# PowerConversionBoard-schematic.net
KiCad netlist of a schematic drawn in EAGLE
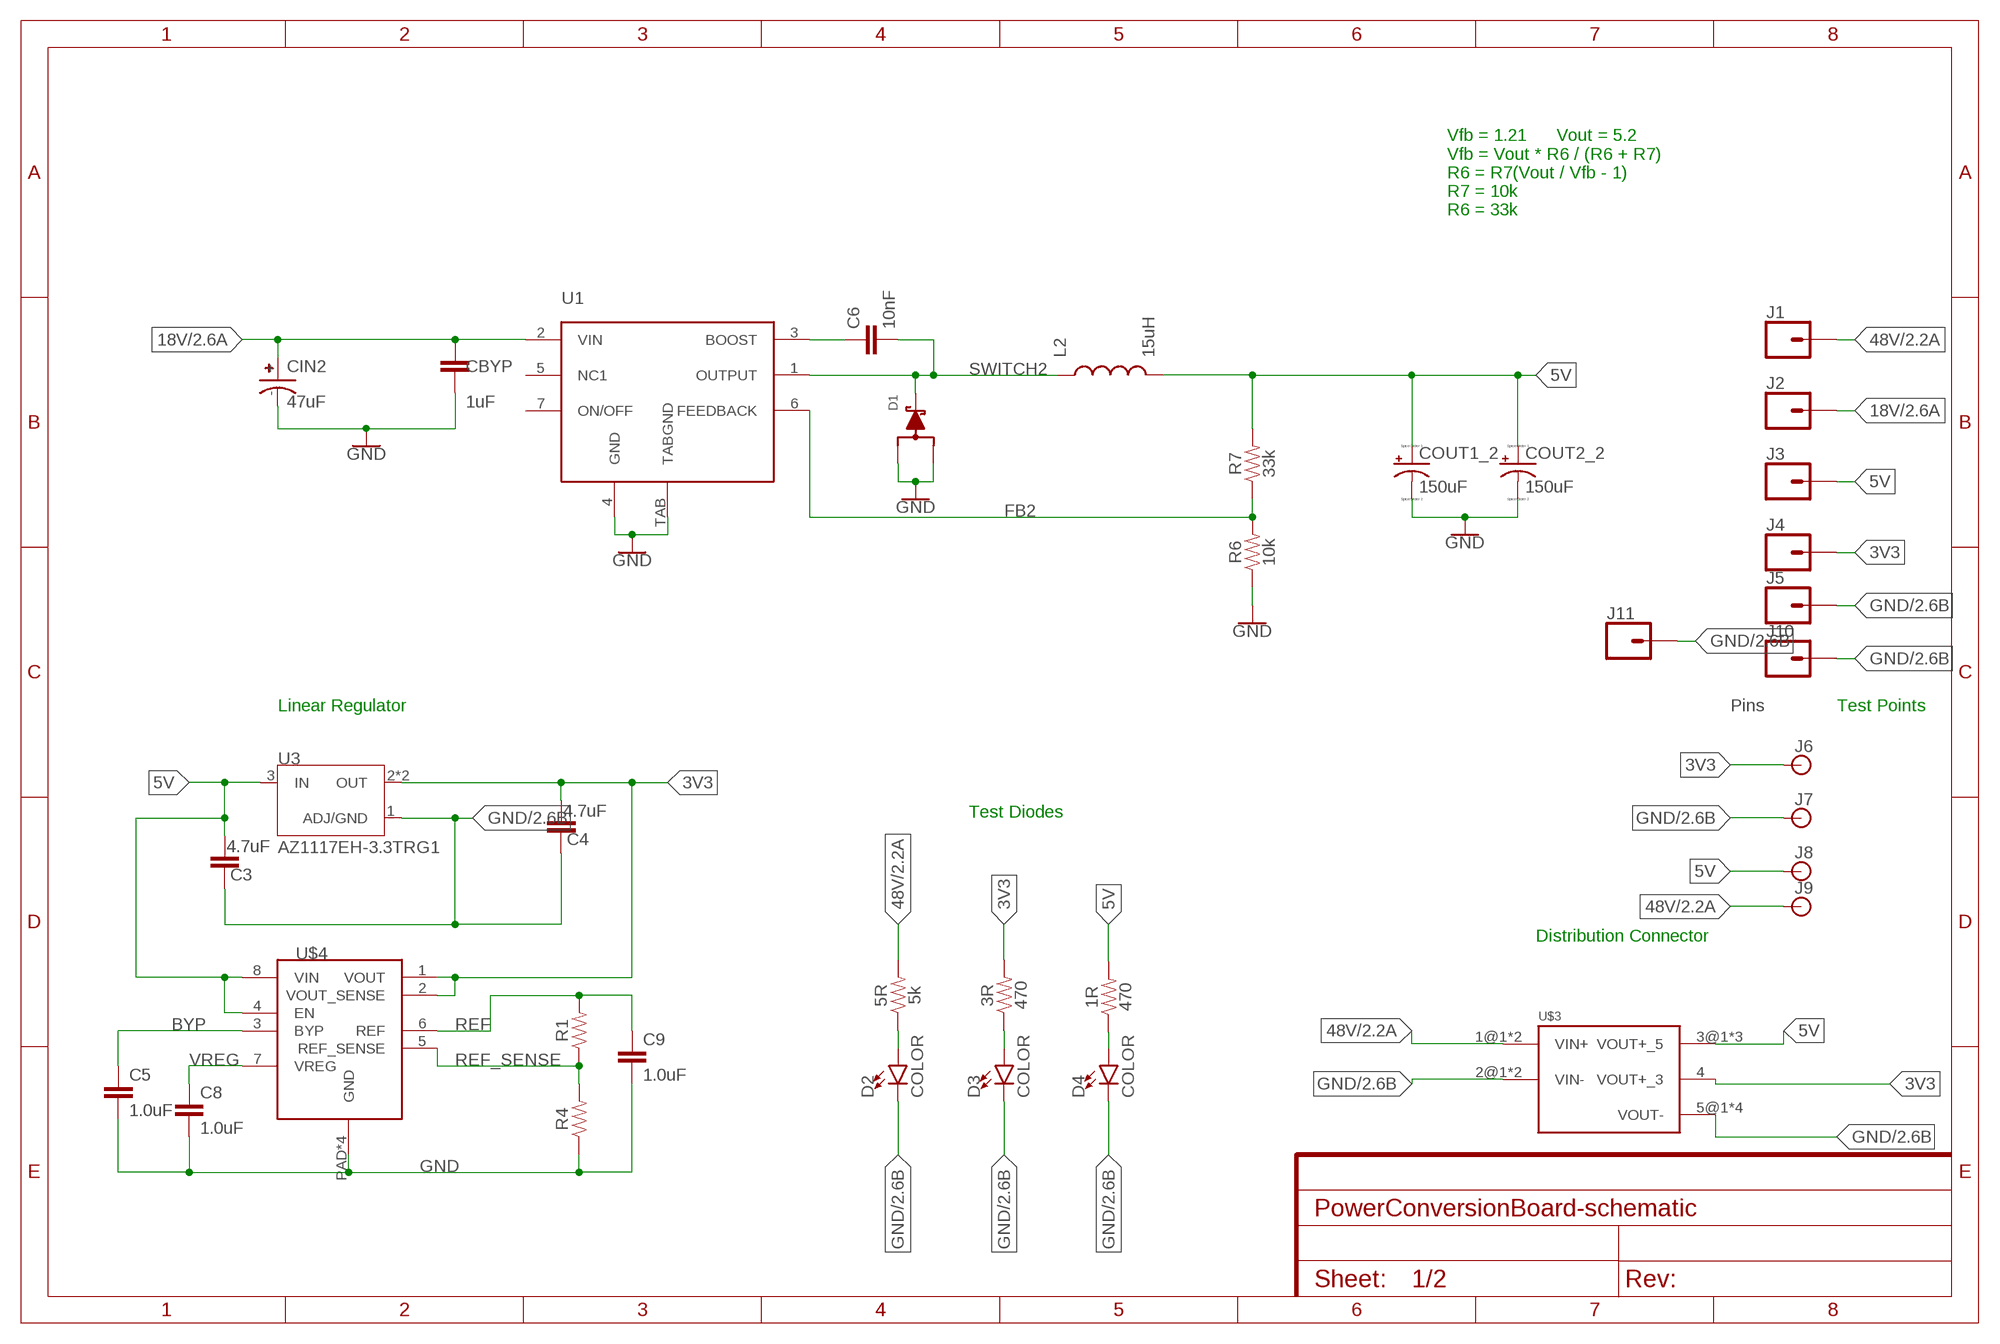
[diagram p0: schematic, sheet 1]
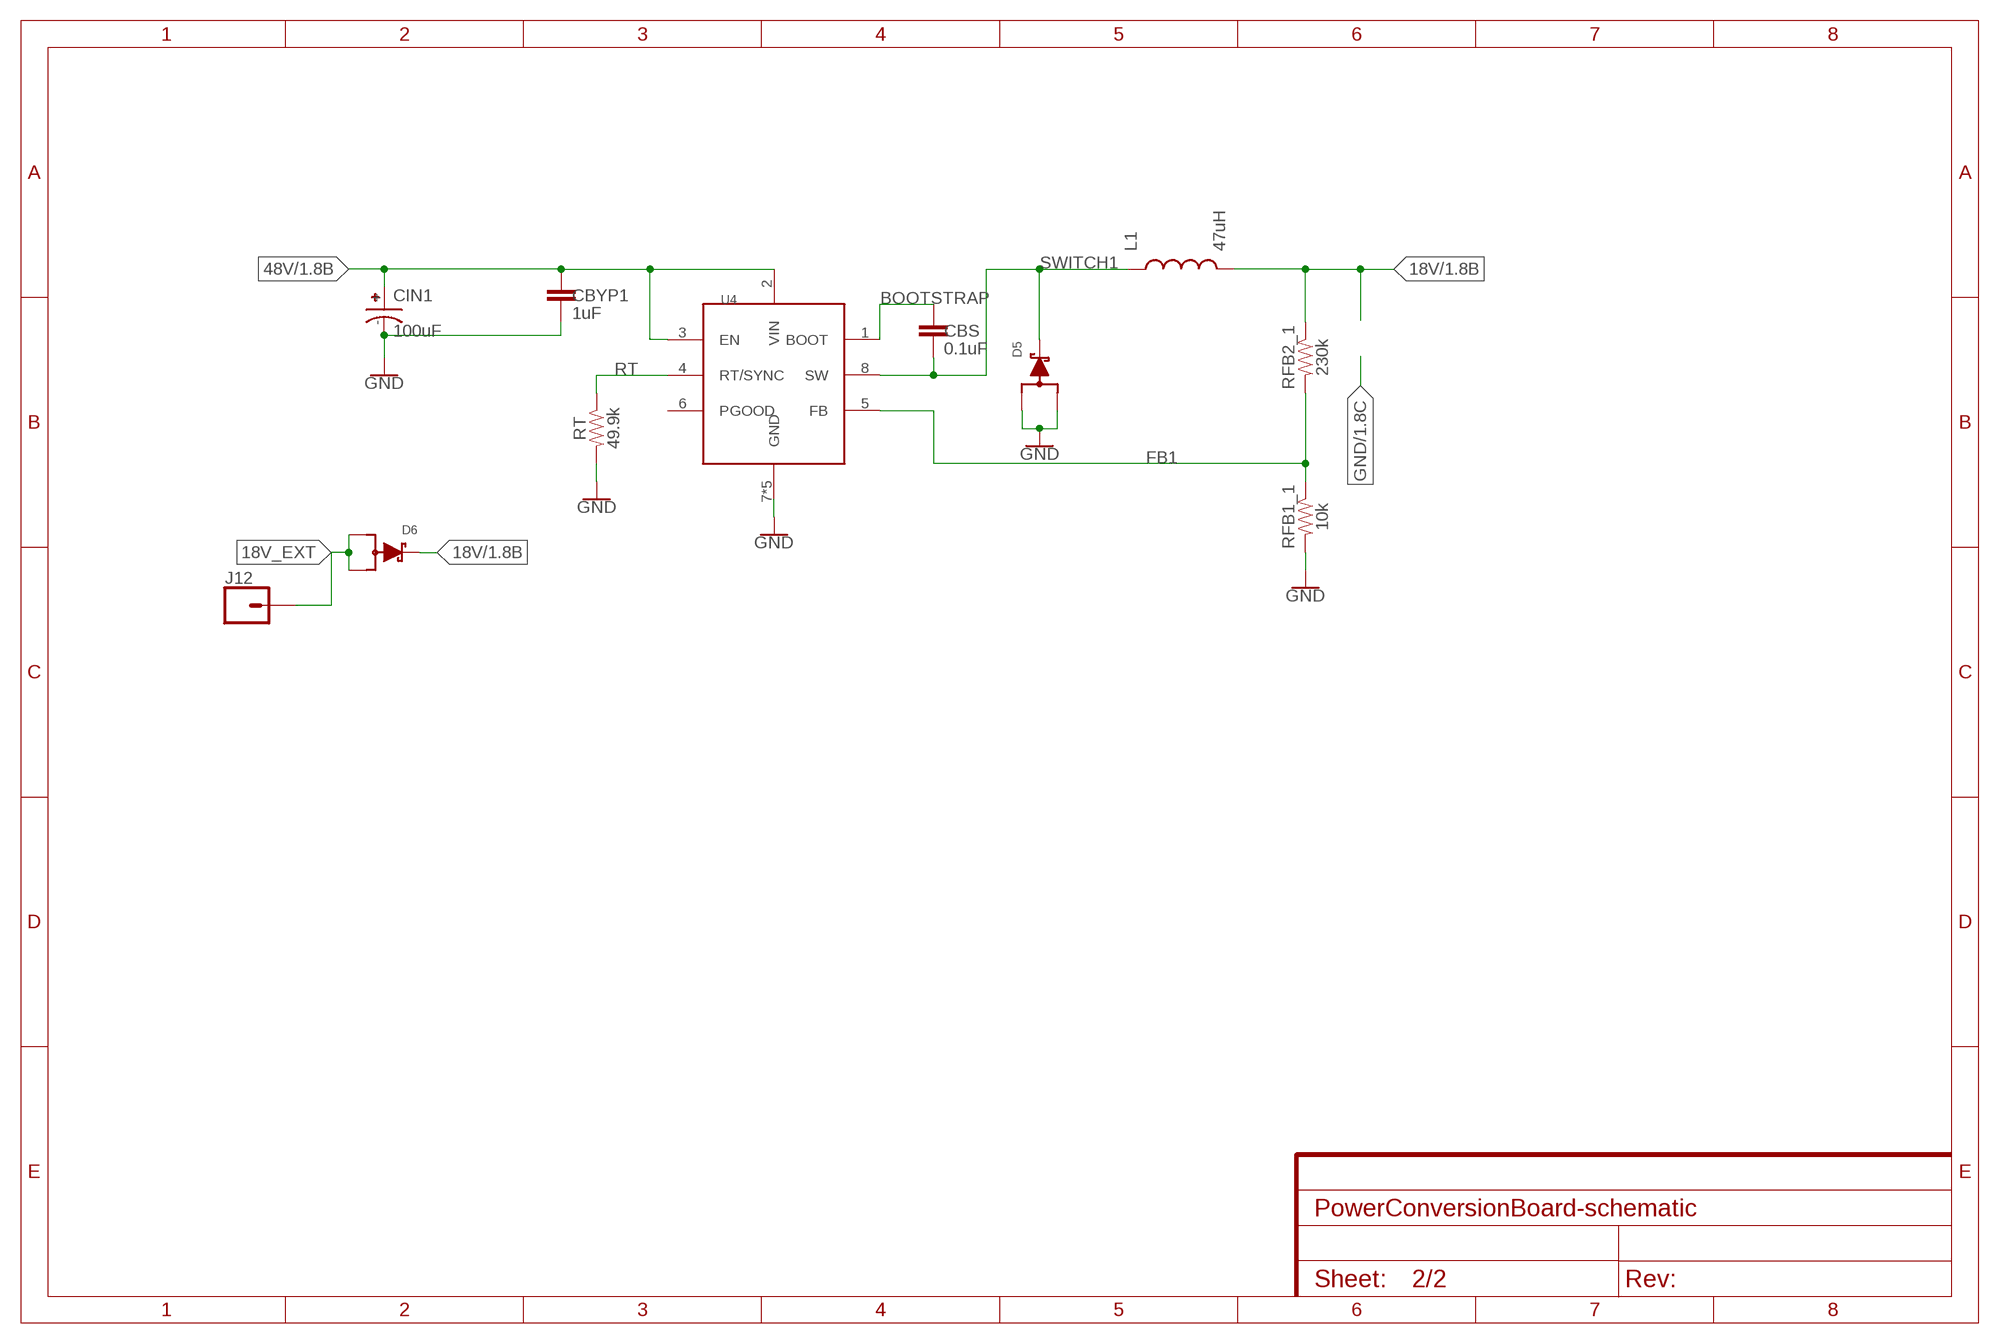
[diagram p1: schematic, sheet 2]

(export (version "E")
  (design (tool "Eeschema 10.0.6"))
  (components
    (comp (ref "CBS")
      (value "0.1uF")
      (footprint "eagle-import:0603")
      (libsource (lib "eagle-import") (part "3.3NF-0603-100V-10%"))
    )
    (comp (ref "CBYP1")
      (value "1uF")
      (footprint "eagle-import:0603")
      (libsource (lib "eagle-import") (part "3.3NF-0603-100V-10%"))
    )
    (comp (ref "CIN1")
      (value "100uF")
      (footprint "eagle-import:CAPAE1030X1050N")
      (fields
        (field (name "ARROW_PART_NUMBER") "UCM1H331MNL1GS")
        (field (name "MOUSER_PART_NUMBER") "647-UCM1H331MNL1GS")
      )
      (libsource (lib "eagle-import") (part "UCM1H331MNL1GS"))
    )
    (comp (ref "D5")
      (value "SWITCHMODE_SCHOTTKY")
      (footprint "eagle-import:DPAK-3")
      (libsource (lib "eagle-import") (part "SWITCHMODE_SCHOTTKY"))
    )
    (comp (ref "D6")
      (value "SWITCHMODE_SCHOTTKY")
      (footprint "eagle-import:DPAK-3")
      (libsource (lib "eagle-import") (part "SWITCHMODE_SCHOTTKY"))
    )
    (comp (ref "J12")
      (value "CONN_01")
      (footprint "eagle-import:1X01")
      (libsource (lib "eagle-import") (part "CONN_01"))
    )
    (comp (ref "L1")
      (value "47uH")
      (footprint "eagle-import:HCMA1305")
      (libsource (lib "eagle-import") (part "HCMA1305"))
    )
    (comp (ref "RFB1_1")
      (value "10k")
      (footprint "eagle-import:0603")
      (libsource (lib "eagle-import") (part "RESISTOR0603"))
    )
    (comp (ref "RFB2_1")
      (value "230k")
      (footprint "eagle-import:0603")
      (libsource (lib "eagle-import") (part "RESISTOR0603"))
    )
    (comp (ref "RT")
      (value "49.9k")
      (footprint "eagle-import:0603")
      (libsource (lib "eagle-import") (part "RESISTOR0603"))
    )
    (comp (ref "U4")
      (value "LMR16020")
      (footprint "eagle-import:8-SOIC-EP")
      (libsource (lib "eagle-import") (part "LMR16020"))
    )
    (comp (ref "1R")
      (value "470")
      (footprint "eagle-import:0603")
      (libsource (lib "eagle-import") (part "470OHM-0603-1/10W-1%"))
    )
    (comp (ref "3R")
      (value "470")
      (footprint "eagle-import:0603")
      (libsource (lib "eagle-import") (part "470OHM-0603-1/10W-1%"))
    )
    (comp (ref "5R")
      (value "5k")
      (footprint "eagle-import:0603")
      (libsource (lib "eagle-import") (part "470OHM-0603-1/10W-1%"))
    )
    (comp (ref "C3")
      (value "4.7uF")
      (footprint "eagle-import:0603")
      (libsource (lib "eagle-import") (part "12PF-0603-50V-5%"))
    )
    (comp (ref "C4")
      (value "4.7uF")
      (footprint "eagle-import:0603")
      (libsource (lib "eagle-import") (part "12PF-0603-50V-5%"))
    )
    (comp (ref "C5")
      (value "1.0uF")
      (footprint "eagle-import:0603")
      (libsource (lib "eagle-import") (part "1.0UF-0603-16V-10%"))
    )
    (comp (ref "C6")
      (value "10nF")
      (footprint "eagle-import:0603")
      (libsource (lib "eagle-import") (part "10NF-0603-50V-10%"))
    )
    (comp (ref "C8")
      (value "1.0uF")
      (footprint "eagle-import:0603")
      (libsource (lib "eagle-import") (part "1.0UF-0603-16V-10%"))
    )
    (comp (ref "C9")
      (value "1.0uF")
      (footprint "eagle-import:0603")
      (libsource (lib "eagle-import") (part "1.0UF-0603-16V-10%"))
    )
    (comp (ref "CBYP")
      (value "1uF")
      (footprint "eagle-import:0603")
      (libsource (lib "eagle-import") (part "3.3NF-0603-100V-10%"))
    )
    (comp (ref "CIN2")
      (value "47uF")
      (footprint "eagle-import:CAPAE1030X1050N")
      (fields
        (field (name "ARROW_PART_NUMBER") "UCM1H331MNL1GS")
        (field (name "MOUSER_PART_NUMBER") "647-UCM1H331MNL1GS")
      )
      (libsource (lib "eagle-import") (part "UCM1H331MNL1GS"))
    )
    (comp (ref "COUT1_2")
      (value "150uF")
      (footprint "eagle-import:CTAN(7.30_4.30MM)")
      (libsource (lib "eagle-import") (part "C-TANTALUM(10UF_150UF)"))
    )
    (comp (ref "COUT2_2")
      (value "150uF")
      (footprint "eagle-import:CTAN(7.30_4.30MM)")
      (libsource (lib "eagle-import") (part "C-TANTALUM(10UF_150UF)"))
    )
    (comp (ref "D1")
      (value "SWITCHMODE_SCHOTTKY")
      (footprint "eagle-import:DPAK-3")
      (libsource (lib "eagle-import") (part "SWITCHMODE_SCHOTTKY"))
    )
    (comp (ref "D2")
      (value "COLOR")
      (footprint "eagle-import:0805")
      (libsource (lib "eagle-import") (part "LED-0805"))
    )
    (comp (ref "D3")
      (value "COLOR")
      (footprint "eagle-import:0805")
      (libsource (lib "eagle-import") (part "LED-0805"))
    )
    (comp (ref "D4")
      (value "COLOR")
      (footprint "eagle-import:0805")
      (libsource (lib "eagle-import") (part "LED-0805"))
    )
    (comp (ref "J1")
      (value "CONN_01")
      (footprint "eagle-import:1X01")
      (libsource (lib "eagle-import") (part "CONN_01"))
    )
    (comp (ref "J2")
      (value "CONN_01")
      (footprint "eagle-import:1X01")
      (libsource (lib "eagle-import") (part "CONN_01"))
    )
    (comp (ref "J3")
      (value "CONN_01")
      (footprint "eagle-import:1X01")
      (libsource (lib "eagle-import") (part "CONN_01"))
    )
    (comp (ref "J4")
      (value "CONN_01")
      (footprint "eagle-import:1X01")
      (libsource (lib "eagle-import") (part "CONN_01"))
    )
    (comp (ref "J5")
      (value "CONN_01")
      (footprint "eagle-import:1X01")
      (libsource (lib "eagle-import") (part "CONN_01"))
    )
    (comp (ref "J6")
      (value "BANANA_PTH")
      (footprint "eagle-import:BANANA_CONN_NO_THERM")
      (libsource (lib "eagle-import") (part "BANANA_PTH"))
    )
    (comp (ref "J7")
      (value "BANANA_PTH")
      (footprint "eagle-import:BANANA_CONN_NO_THERM")
      (libsource (lib "eagle-import") (part "BANANA_PTH"))
    )
    (comp (ref "J8")
      (value "BANANA_PTH")
      (footprint "eagle-import:BANANA_CONN_NO_THERM")
      (libsource (lib "eagle-import") (part "BANANA_PTH"))
    )
    (comp (ref "J9")
      (value "BANANA_PTH")
      (footprint "eagle-import:BANANA_CONN_NO_THERM")
      (libsource (lib "eagle-import") (part "BANANA_PTH"))
    )
    (comp (ref "J10")
      (value "CONN_01")
      (footprint "eagle-import:1X01")
      (libsource (lib "eagle-import") (part "CONN_01"))
    )
    (comp (ref "J11")
      (value "CONN_01")
      (footprint "eagle-import:1X01")
      (libsource (lib "eagle-import") (part "CONN_01"))
    )
    (comp (ref "L2")
      (value "15uH")
      (footprint "eagle-import:HCMA1305")
      (libsource (lib "eagle-import") (part "HCMA1305"))
    )
    (comp (ref "R1")
      (value "RESISTOR0603")
      (footprint "eagle-import:0603")
      (libsource (lib "eagle-import") (part "RESISTOR0603"))
    )
    (comp (ref "R4")
      (value "RESISTOR0603")
      (footprint "eagle-import:0603")
      (libsource (lib "eagle-import") (part "RESISTOR0603"))
    )
    (comp (ref "R6")
      (value "10k")
      (footprint "eagle-import:0603")
      (libsource (lib "eagle-import") (part "10KOHM-0603-1/10W-1%"))
    )
    (comp (ref "R7")
      (value "33k")
      (footprint "eagle-import:0603")
      (libsource (lib "eagle-import") (part "33KOHM-0603-1/10W-1%"))
    )
    (comp (ref "U$3")
      (value "CON2DIST")
      (footprint "eagle-import:CON2DIST")
      (libsource (lib "eagle-import") (part "CON2DIST"))
    )
    (comp (ref "U$4")
      (value "ADP7159ARDZ-04-R7")
      (footprint "eagle-import:8-SOIC-EP")
      (libsource (lib "eagle-import") (part "ADP7159ARDZ-04-R7"))
    )
    (comp (ref "U1")
      (value "LM2678")
      (footprint "eagle-import:D2PAK_TO-263")
      (libsource (lib "eagle-import") (part "LM2678"))
    )
    (comp (ref "U3")
      (value "AZ1117EH-3.3TRG1")
      (footprint "eagle-import:SOT230P700X180-4N")
      (fields (field (name "MF") "Diodes Inc."))
      (libsource (lib "eagle-import") (part "AZ1117EH-3.3TRG1"))
    )
  )
  (nets
    (net (code "1") (name "3V3") (class "Default")
      (node (ref "3R") (pin "2") (pinfunction "2_2") (pintype "passive"))
      (node (ref "C4") (pin "1") (pinfunction "1_1") (pintype "passive"))
      (node (ref "J4") (pin "1") (pinfunction "1_1") (pintype "passive"))
      (node (ref "J6") (pin "1") (pinfunction "1_1") (pintype "passive"))
      (node (ref "U$3") (pin "4") (pinfunction "VOUT+_3_4") (pintype "bidirectional"))
      (node (ref "U$4") (pin "1") (pinfunction "VOUT_1") (pintype "bidirectional"))
      (node (ref "U$4") (pin "2") (pinfunction "VOUT_SENSE_2") (pintype "bidirectional"))
      (node (ref "U3") (pin "2") (pinfunction "OUT_2") (pintype "output"))
      (node (ref "U3") (pin "4") (pinfunction "OUT_4") (pintype "output"))
    )
    (net (code "2") (name "5V") (class "Default")
      (node (ref "1R") (pin "2") (pinfunction "2_2") (pintype "passive"))
      (node (ref "C3") (pin "1") (pinfunction "1_1") (pintype "passive"))
      (node (ref "COUT1_2") (pin "+") (pinfunction "+_+") (pintype "passive"))
      (node (ref "COUT2_2") (pin "+") (pinfunction "+_+") (pintype "passive"))
      (node (ref "J3") (pin "1") (pinfunction "1_1") (pintype "passive"))
      (node (ref "J8") (pin "1") (pinfunction "1_1") (pintype "passive"))
      (node (ref "L2") (pin "2") (pinfunction "2_2") (pintype "passive"))
      (node (ref "R7") (pin "2") (pinfunction "2_2") (pintype "passive"))
      (node (ref "U$3") (pin "3@1") (pinfunction "VOUT+_5_3@1") (pintype "bidirectional"))
      (node (ref "U$3") (pin "3@2") (pinfunction "VOUT+_5_3@2") (pintype "bidirectional"))
      (node (ref "U$3") (pin "3@3") (pinfunction "VOUT+_5_3@3") (pintype "bidirectional"))
      (node (ref "U$4") (pin "4") (pinfunction "EN_4") (pintype "bidirectional"))
      (node (ref "U$4") (pin "8") (pinfunction "VIN_8") (pintype "bidirectional"))
      (node (ref "U3") (pin "3") (pinfunction "IN_3") (pintype "input"))
    )
    (net (code "3") (name "18V") (class "Default")
      (node (ref "CBYP") (pin "1") (pinfunction "1_1") (pintype "passive"))
      (node (ref "CIN2") (pin "+") (pinfunction "+_+") (pintype "bidirectional"))
      (node (ref "D6") (pin "4") (pinfunction "C_4") (pintype "bidirectional"))
      (node (ref "J2") (pin "1") (pinfunction "1_1") (pintype "passive"))
      (node (ref "L1") (pin "2") (pinfunction "2_2") (pintype "passive"))
      (node (ref "RFB2_1") (pin "1") (pinfunction "1_1") (pintype "passive"))
      (node (ref "U1") (pin "2") (pinfunction "VIN_2") (pintype "power_in"))
    )
    (net (code "4") (name "18V_EXT") (class "Default")
      (node (ref "D6") (pin "1") (pinfunction "A_1") (pintype "bidirectional"))
      (node (ref "D6") (pin "3") (pinfunction "A_3") (pintype "bidirectional"))
      (node (ref "J12") (pin "1") (pinfunction "1_1") (pintype "passive"))
    )
    (net (code "5") (name "48V") (class "Default")
      (node (ref "5R") (pin "2") (pinfunction "2_2") (pintype "passive"))
      (node (ref "CBYP1") (pin "1") (pinfunction "1_1") (pintype "passive"))
      (node (ref "CIN1") (pin "+") (pinfunction "+_+") (pintype "bidirectional"))
      (node (ref "J1") (pin "1") (pinfunction "1_1") (pintype "passive"))
      (node (ref "J9") (pin "1") (pinfunction "1_1") (pintype "passive"))
      (node (ref "U$3") (pin "1@1") (pinfunction "VIN+_1@1") (pintype "bidirectional"))
      (node (ref "U$3") (pin "1@2") (pinfunction "VIN+_1@2") (pintype "bidirectional"))
      (node (ref "U4") (pin "2") (pinfunction "VIN_2") (pintype "power_in"))
      (node (ref "U4") (pin "3") (pinfunction "EN_3") (pintype "input"))
    )
    (net (code "6") (name "BOOTSTRAP") (class "Default")
      (node (ref "CBS") (pin "1") (pinfunction "1_1") (pintype "passive"))
      (node (ref "U4") (pin "1") (pinfunction "BOOT_1") (pintype "passive"))
    )
    (net (code "7") (name "BYP") (class "Default")
      (node (ref "C5") (pin "1") (pinfunction "1_1") (pintype "passive"))
      (node (ref "U$4") (pin "3") (pinfunction "BYP_3") (pintype "bidirectional"))
    )
    (net (code "8") (name "FB1") (class "Default")
      (node (ref "RFB1_1") (pin "1") (pinfunction "1_1") (pintype "passive"))
      (node (ref "RFB2_1") (pin "2") (pinfunction "2_2") (pintype "passive"))
      (node (ref "U4") (pin "5") (pinfunction "FB_5") (pintype "input"))
    )
    (net (code "9") (name "FB2") (class "Default")
      (node (ref "R6") (pin "2") (pinfunction "2_2") (pintype "passive"))
      (node (ref "R7") (pin "1") (pinfunction "1_1") (pintype "passive"))
      (node (ref "U1") (pin "6") (pinfunction "FEEDBACK_6") (pintype "input"))
    )
    (net (code "10") (name "GND") (class "Default")
      (node (ref "C3") (pin "2") (pinfunction "2_2") (pintype "passive"))
      (node (ref "C4") (pin "2") (pinfunction "2_2") (pintype "passive"))
      (node (ref "C5") (pin "2") (pinfunction "2_2") (pintype "passive"))
      (node (ref "C8") (pin "2") (pinfunction "2_2") (pintype "passive"))
      (node (ref "C9") (pin "2") (pinfunction "2_2") (pintype "passive"))
      (node (ref "CBYP") (pin "2") (pinfunction "2_2") (pintype "passive"))
      (node (ref "CBYP1") (pin "2") (pinfunction "2_2") (pintype "passive"))
      (node (ref "CIN1") (pin "-") (pinfunction "-_-") (pintype "bidirectional"))
      (node (ref "CIN2") (pin "-") (pinfunction "-_-") (pintype "bidirectional"))
      (node (ref "COUT1_2") (pin "-") (pinfunction "-_-") (pintype "passive"))
      (node (ref "COUT2_2") (pin "-") (pinfunction "-_-") (pintype "passive"))
      (node (ref "D1") (pin "1") (pinfunction "A_1") (pintype "bidirectional"))
      (node (ref "D1") (pin "3") (pinfunction "A_3") (pintype "bidirectional"))
      (node (ref "D2") (pin "C") (pinfunction "C_C") (pintype "passive"))
      (node (ref "D3") (pin "C") (pinfunction "C_C") (pintype "passive"))
      (node (ref "D4") (pin "C") (pinfunction "C_C") (pintype "passive"))
      (node (ref "D5") (pin "1") (pinfunction "A_1") (pintype "bidirectional"))
      (node (ref "D5") (pin "3") (pinfunction "A_3") (pintype "bidirectional"))
      (node (ref "J10") (pin "1") (pinfunction "1_1") (pintype "passive"))
      (node (ref "J11") (pin "1") (pinfunction "1_1") (pintype "passive"))
      (node (ref "J5") (pin "1") (pinfunction "1_1") (pintype "passive"))
      (node (ref "J7") (pin "1") (pinfunction "1_1") (pintype "passive"))
      (node (ref "R4") (pin "1") (pinfunction "1_1") (pintype "passive"))
      (node (ref "R6") (pin "1") (pinfunction "1_1") (pintype "passive"))
      (node (ref "RFB1_1") (pin "2") (pinfunction "2_2") (pintype "passive"))
      (node (ref "RT") (pin "2") (pinfunction "2_2") (pintype "passive"))
      (node (ref "U$3") (pin "2@1") (pinfunction "VIN-_2@1") (pintype "bidirectional"))
      (node (ref "U$3") (pin "2@2") (pinfunction "VIN-_2@2") (pintype "bidirectional"))
      (node (ref "U$3") (pin "5@1") (pinfunction "VOUT-_5@1") (pintype "bidirectional"))
      (node (ref "U$3") (pin "5@2") (pinfunction "VOUT-_5@2") (pintype "bidirectional"))
      (node (ref "U$3") (pin "5@3") (pinfunction "VOUT-_5@3") (pintype "bidirectional"))
      (node (ref "U$3") (pin "5@4") (pinfunction "VOUT-_5@4") (pintype "bidirectional"))
      (node (ref "U$4") (pin "PAD") (pinfunction "GND_PAD") (pintype "bidirectional"))
      (node (ref "U$4") (pin "PAD_BOT") (pinfunction "GND_PAD_BOT") (pintype "bidirectional"))
      (node (ref "U$4") (pin "PAD_VIA1") (pinfunction "GND_PAD_VIA1") (pintype "bidirectional"))
      (node (ref "U$4") (pin "PAD_VIA2") (pinfunction "GND_PAD_VIA2") (pintype "bidirectional"))
      (node (ref "U1") (pin "4") (pinfunction "GND_4") (pintype "power_in"))
      (node (ref "U1") (pin "TAB") (pinfunction "TABGND_TAB") (pintype "power_in"))
      (node (ref "U3") (pin "1") (pinfunction "ADJ/GND_1") (pintype "power_in"))
      (node (ref "U4") (pin "7") (pinfunction "GND_7") (pintype "power_in"))
      (node (ref "U4") (pin "PAD") (pinfunction "GND_PAD") (pintype "power_in"))
      (node (ref "U4") (pin "PAD_BOT") (pinfunction "GND_PAD_BOT") (pintype "power_in"))
      (node (ref "U4") (pin "PAD_VIA1") (pinfunction "GND_PAD_VIA1") (pintype "power_in"))
      (node (ref "U4") (pin "PAD_VIA2") (pinfunction "GND_PAD_VIA2") (pintype "power_in"))
    )
    (net (code "11") (name "Net-(1R-Pad1)") (class "Default")
      (node (ref "1R") (pin "1") (pinfunction "1_1") (pintype "passive"))
      (node (ref "D4") (pin "A") (pinfunction "A_A") (pintype "passive"))
    )
    (net (code "12") (name "Net-(3R-Pad1)") (class "Default")
      (node (ref "3R") (pin "1") (pinfunction "1_1") (pintype "passive"))
      (node (ref "D3") (pin "A") (pinfunction "A_A") (pintype "passive"))
    )
    (net (code "13") (name "Net-(5R-Pad1)") (class "Default")
      (node (ref "5R") (pin "1") (pinfunction "1_1") (pintype "passive"))
      (node (ref "D2") (pin "A") (pinfunction "A_A") (pintype "passive"))
    )
    (net (code "14") (name "Net-(U1-BOOST)") (class "Default")
      (node (ref "C6") (pin "1") (pinfunction "1_1") (pintype "passive"))
      (node (ref "U1") (pin "3") (pinfunction "BOOST_3") (pintype "bidirectional"))
    )
    (net (code "15") (name "REF") (class "Default")
      (node (ref "C9") (pin "1") (pinfunction "1_1") (pintype "passive"))
      (node (ref "R1") (pin "2") (pinfunction "2_2") (pintype "passive"))
      (node (ref "U$4") (pin "6") (pinfunction "REF_6") (pintype "bidirectional"))
    )
    (net (code "16") (name "REF_SENSE") (class "Default")
      (node (ref "R1") (pin "1") (pinfunction "1_1") (pintype "passive"))
      (node (ref "R4") (pin "2") (pinfunction "2_2") (pintype "passive"))
      (node (ref "U$4") (pin "5") (pinfunction "REF_SENSE_5") (pintype "bidirectional"))
    )
    (net (code "17") (name "RT") (class "Default")
      (node (ref "RT") (pin "1") (pinfunction "1_1") (pintype "passive"))
      (node (ref "U4") (pin "4") (pinfunction "RT/SYNC_4") (pintype "input"))
    )
    (net (code "18") (name "SWITCH1") (class "Default")
      (node (ref "CBS") (pin "2") (pinfunction "2_2") (pintype "passive"))
      (node (ref "D5") (pin "4") (pinfunction "C_4") (pintype "bidirectional"))
      (node (ref "L1") (pin "1") (pinfunction "1_1") (pintype "passive"))
      (node (ref "U4") (pin "8") (pinfunction "SW_8") (pintype "output"))
    )
    (net (code "19") (name "SWITCH2") (class "Default")
      (node (ref "C6") (pin "2") (pinfunction "2_2") (pintype "passive"))
      (node (ref "D1") (pin "4") (pinfunction "C_4") (pintype "bidirectional"))
      (node (ref "L2") (pin "1") (pinfunction "1_1") (pintype "passive"))
      (node (ref "U1") (pin "1") (pinfunction "OUTPUT_1") (pintype "output"))
    )
    (net (code "20") (name "VREG") (class "Default")
      (node (ref "C8") (pin "1") (pinfunction "1_1") (pintype "passive"))
      (node (ref "U$4") (pin "7") (pinfunction "VREG_7") (pintype "bidirectional"))
    )
    (net (code "21") (name "unconnected-(U1-NC1-Pad5)") (class "Default")
      (node (ref "U1") (pin "5") (pinfunction "NC1_5") (pintype "no_connect"))
    )
    (net (code "22") (name "unconnected-(U1-ON{slash}OFF-Pad7)") (class "Default")
      (node (ref "U1") (pin "7") (pinfunction "ON/OFF_7") (pintype "input"))
    )
    (net (code "23") (name "unconnected-(U4-PGOOD-Pad6)") (class "Default")
      (node (ref "U4") (pin "6") (pinfunction "PGOOD_6") (pintype "output"))
    )
  )
)
